# AST1012.net
KiCad netlist of a schematic drawn in EAGLE
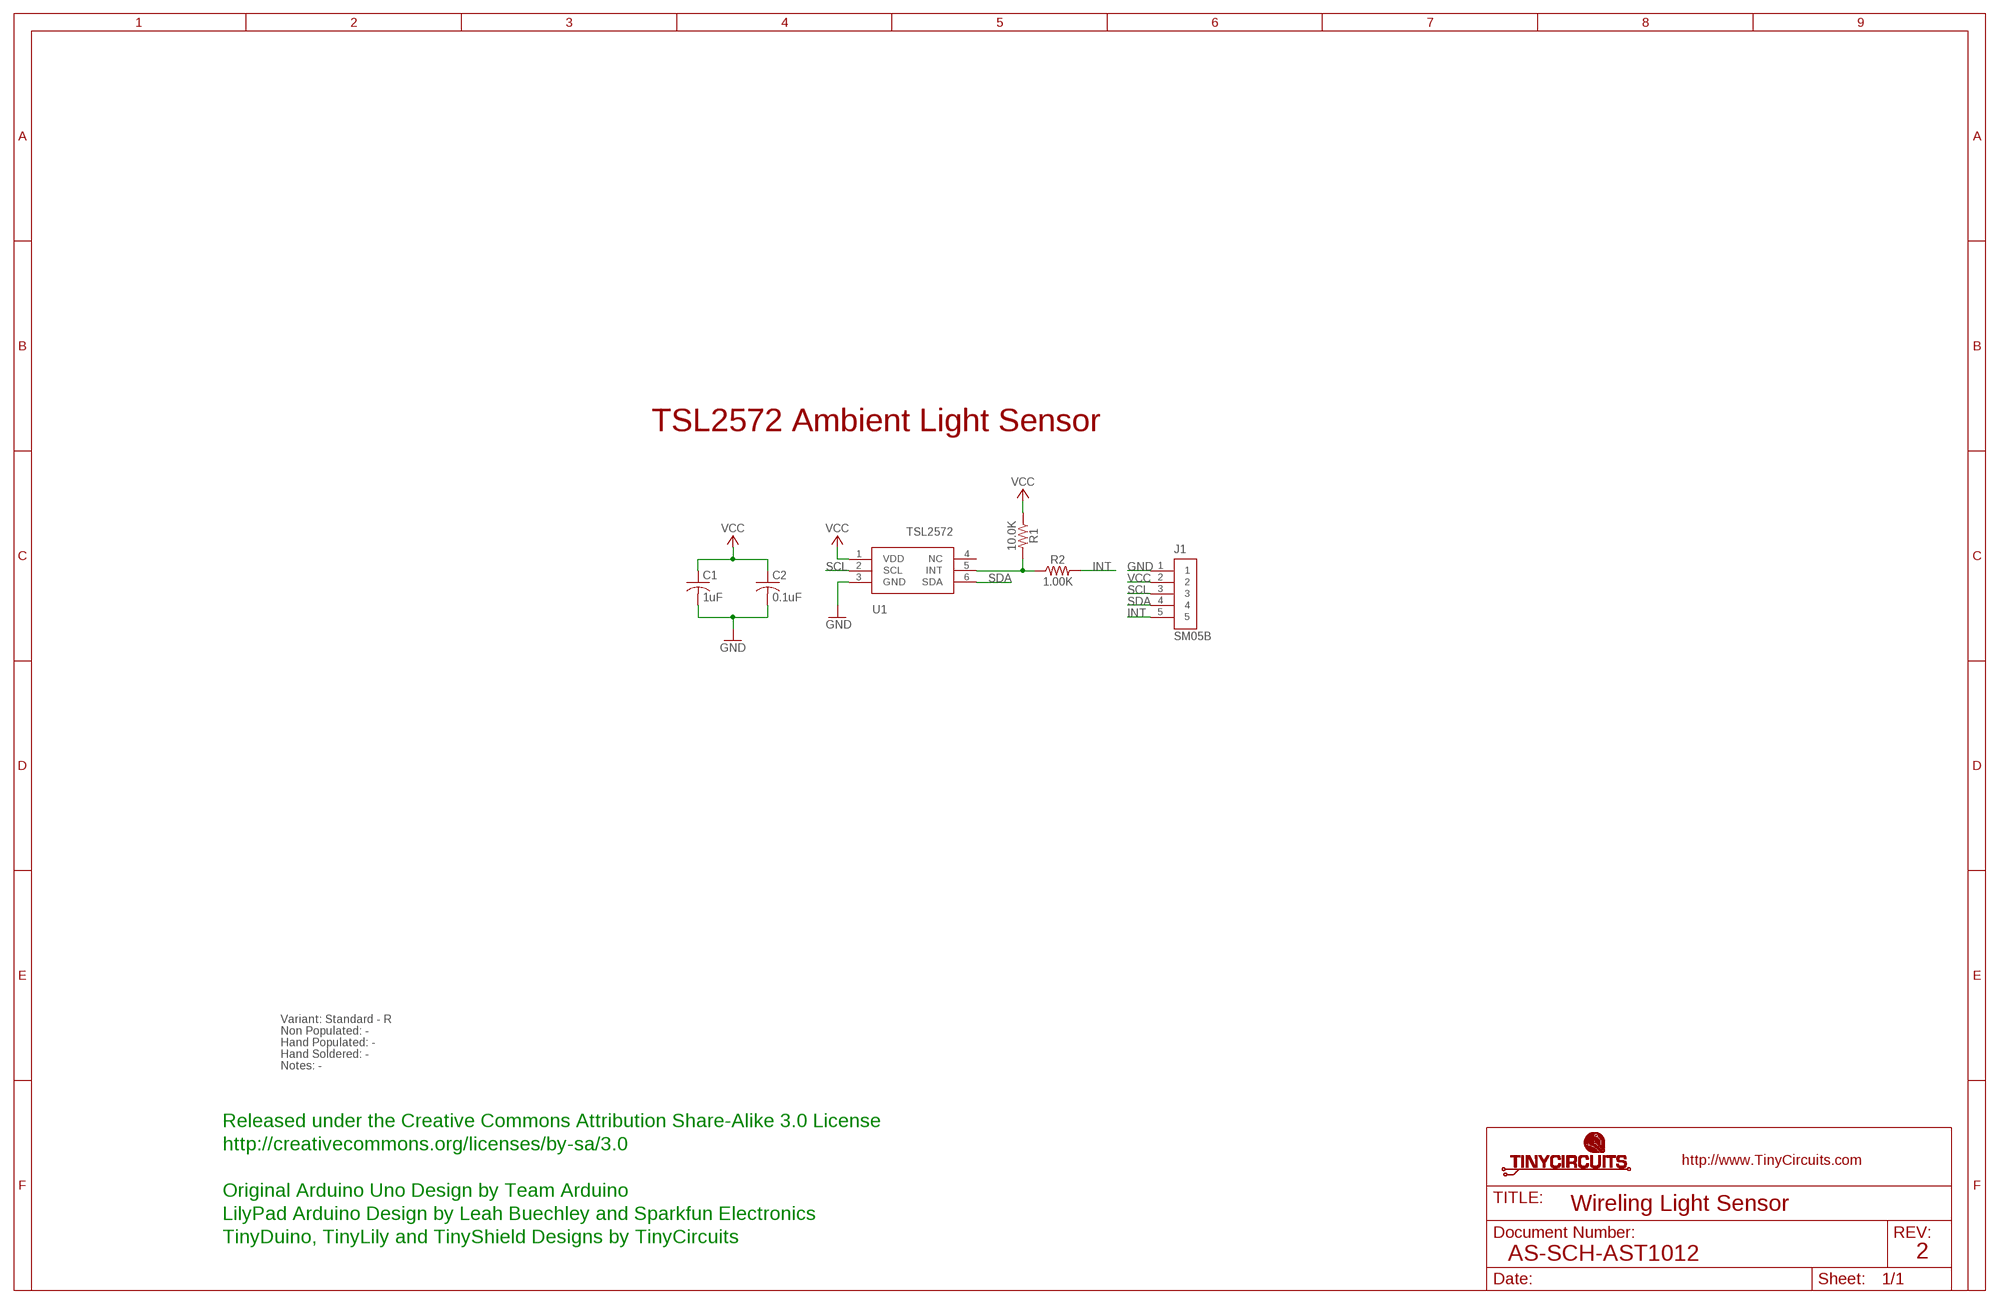
[diagram p0: schematic, sheet 1]

(export (version "E")
  (design (tool "Eeschema 10.0.6"))
  (components
    (comp (ref "C1")
      (value "1uF")
      (footprint "eagle-import:C0603")
      (fields (field (name "PARTNO") "AS-ITM-00410") (field (name "PARTNO_1") "AS-ITM-00410"))
      (libsource (lib "eagle-import") (part "AS-ITM-00410"))
    )
    (comp (ref "C2")
      (value "0.1uF")
      (footprint "eagle-import:C0402")
      (fields (field (name "PARTNO") "AS-ITM-00008"))
      (libsource (lib "eagle-import") (part "AS-ITM-00008"))
    )
    (comp (ref "J1")
      (value "SM05B")
      (footprint "eagle-import:JST_SH_5X1_EDGE")
      (fields (field (name "PARTNO") "AS-ITM-00340"))
      (libsource (lib "eagle-import") (part "AS-ITM-00340EDGE"))
    )
    (comp (ref "R1")
      (value "10.0K")
      (footprint "eagle-import:0402")
      (fields (field (name "PARTNO") "AS-ITM-00032") (field (name "PARTNO_1") "AS-ITM-00032"))
      (libsource (lib "eagle-import") (part "AS-ITM-00032"))
    )
    (comp (ref "R2")
      (value "1.00K")
      (footprint "eagle-import:0402")
      (fields (field (name "PARTNO") "AS-ITM-00003") (field (name "PARTNO_1") "AS-ITM-00003"))
      (libsource (lib "eagle-import") (part "AS-ITM-00003"))
    )
    (comp (ref "U1")
      (value "TSL2572")
      (footprint "eagle-import:TSL2572")
      (fields (field (name "PARTNO") "AS-ITM-00116") (field (name "PARTNO_1") "AS-ITM-00116"))
      (libsource (lib "eagle-import") (part "AS-ITM-00116"))
    )
  )
  (nets
    (net (code "1") (name "/INT") (class "Default")
      (node (ref "J1") (pin "5") (pinfunction "5_5") (pintype "bidirectional"))
      (node (ref "R2") (pin "2") (pinfunction "2_2") (pintype "passive"))
    )
    (net (code "2") (name "/SCL") (class "Default")
      (node (ref "J1") (pin "3") (pinfunction "3_3") (pintype "bidirectional"))
      (node (ref "U1") (pin "2") (pinfunction "SCL_2") (pintype "bidirectional"))
    )
    (net (code "3") (name "/SDA") (class "Default")
      (node (ref "J1") (pin "4") (pinfunction "4_4") (pintype "bidirectional"))
      (node (ref "U1") (pin "6") (pinfunction "SDA_6") (pintype "bidirectional"))
    )
    (net (code "4") (name "GND") (class "Default")
      (node (ref "C1") (pin "2") (pinfunction "2_2") (pintype "passive"))
      (node (ref "C2") (pin "2") (pinfunction "2_2") (pintype "passive"))
      (node (ref "J1") (pin "1") (pinfunction "1_1") (pintype "bidirectional"))
      (node (ref "U1") (pin "3") (pinfunction "GND_3") (pintype "bidirectional"))
    )
    (net (code "5") (name "Net-(U1-INT)") (class "Default")
      (node (ref "R1") (pin "2") (pinfunction "2_2") (pintype "passive"))
      (node (ref "R2") (pin "1") (pinfunction "1_1") (pintype "passive"))
      (node (ref "U1") (pin "5") (pinfunction "INT_5") (pintype "bidirectional"))
    )
    (net (code "6") (name "VCC") (class "Default")
      (node (ref "C1") (pin "1") (pinfunction "1_1") (pintype "passive"))
      (node (ref "C2") (pin "1") (pinfunction "1_1") (pintype "passive"))
      (node (ref "J1") (pin "2") (pinfunction "2_2") (pintype "bidirectional"))
      (node (ref "R1") (pin "1") (pinfunction "1_1") (pintype "passive"))
      (node (ref "U1") (pin "1") (pinfunction "VDD_1") (pintype "bidirectional"))
    )
    (net (code "7") (name "unconnected-(U1-NC-Pad4)") (class "Default")
      (node (ref "U1") (pin "4") (pinfunction "NC_4") (pintype "bidirectional"))
    )
  )
)
